# Ex_FTDI_Cable.net
KiCad netlist of a schematic drawn in EAGLE
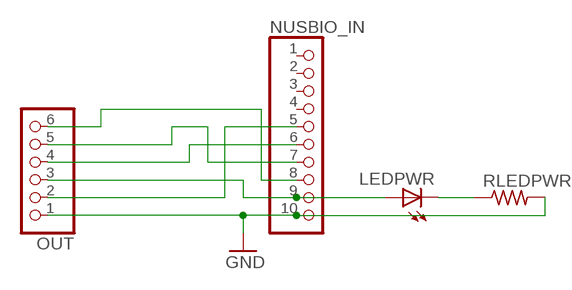
[diagram p0: schematic, sheet 1]

(export (version "E")
  (design (tool "Eeschema 10.0.6"))
  (components
    (comp (ref "LEDPWR")
      (value "LEDCHIPLED_0805")
      (footprint "eagle-import:CHIPLED_0805")
      (libsource (lib "eagle-import") (part "LEDCHIPLED_0805"))
    )
    (comp (ref "NUSBIO_IN")
      (value "PINHD-1X10")
      (footprint "eagle-import:1X10-BIG")
      (libsource (lib "eagle-import") (part "PINHD-1X10"))
    )
    (comp (ref "OUT")
      (value "PINHD-1X6")
      (footprint "eagle-import:1X06")
      (libsource (lib "eagle-import") (part "PINHD-1X6"))
    )
    (comp (ref "RLEDPWR")
      (value "R-US_R0805")
      (footprint "eagle-import:R0805")
      (libsource (lib "eagle-import") (part "R-US_R0805"))
    )
  )
  (nets
    (net (code "1") (name "GND") (class "Default")
      (node (ref "NUSBIO_IN") (pin "10") (pinfunction "10_10") (pintype "passive"))
      (node (ref "OUT") (pin "1") (pinfunction "1_1") (pintype "passive"))
      (node (ref "RLEDPWR") (pin "2") (pinfunction "2_2") (pintype "passive"))
    )
    (net (code "2") (name "Net-(LEDPWR-PadA)") (class "Default")
      (node (ref "LEDPWR") (pin "A") (pinfunction "A_A") (pintype "passive"))
      (node (ref "NUSBIO_IN") (pin "9") (pinfunction "9_9") (pintype "passive"))
      (node (ref "OUT") (pin "3") (pinfunction "3_3") (pintype "passive"))
    )
    (net (code "3") (name "Net-(LEDPWR-PadC)") (class "Default")
      (node (ref "LEDPWR") (pin "C") (pinfunction "C_C") (pintype "passive"))
      (node (ref "RLEDPWR") (pin "1") (pinfunction "1_1") (pintype "passive"))
    )
    (net (code "4") (name "Net-(NUSBIO_IN-Pad5)") (class "Default")
      (node (ref "NUSBIO_IN") (pin "5") (pinfunction "5_5") (pintype "passive"))
      (node (ref "OUT") (pin "2") (pinfunction "2_2") (pintype "passive"))
    )
    (net (code "5") (name "Net-(NUSBIO_IN-Pad6)") (class "Default")
      (node (ref "NUSBIO_IN") (pin "6") (pinfunction "6_6") (pintype "passive"))
      (node (ref "OUT") (pin "4") (pinfunction "4_4") (pintype "passive"))
    )
    (net (code "6") (name "Net-(NUSBIO_IN-Pad7)") (class "Default")
      (node (ref "NUSBIO_IN") (pin "7") (pinfunction "7_7") (pintype "passive"))
      (node (ref "OUT") (pin "5") (pinfunction "5_5") (pintype "passive"))
    )
    (net (code "7") (name "Net-(NUSBIO_IN-Pad8)") (class "Default")
      (node (ref "NUSBIO_IN") (pin "8") (pinfunction "8_8") (pintype "passive"))
      (node (ref "OUT") (pin "6") (pinfunction "6_6") (pintype "passive"))
    )
    (net (code "8") (name "unconnected-(NUSBIO_IN-Pad1)") (class "Default")
      (node (ref "NUSBIO_IN") (pin "1") (pinfunction "1_1") (pintype "passive"))
    )
    (net (code "9") (name "unconnected-(NUSBIO_IN-Pad2)") (class "Default")
      (node (ref "NUSBIO_IN") (pin "2") (pinfunction "2_2") (pintype "passive"))
    )
    (net (code "10") (name "unconnected-(NUSBIO_IN-Pad3)") (class "Default")
      (node (ref "NUSBIO_IN") (pin "3") (pinfunction "3_3") (pintype "passive"))
    )
    (net (code "11") (name "unconnected-(NUSBIO_IN-Pad4)") (class "Default")
      (node (ref "NUSBIO_IN") (pin "4") (pinfunction "4_4") (pintype "passive"))
    )
  )
)
